# Power_Domain.net
KiCad netlist of a schematic drawn in Altium Designer
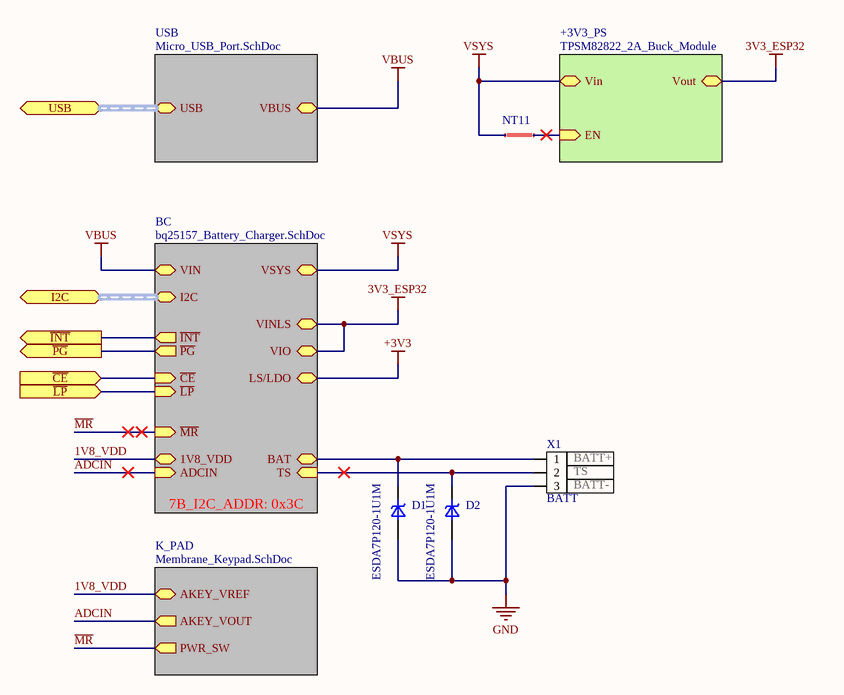
[diagram p0: Power_Domain.SchDoc]

(export (version "E")
  (design (tool "Eeschema 10.0.6"))
  (components
    (comp (ref "D1")
      (value "ESDA7P120-1U1M")
      (footprint "ST_QFN_1610")
      (description "11.5V Clamp 120A (8/20µs) Ipp Tvs Diode Surface Mount 1610")
      (fields (field (name "MANUFACTURER") "STMicroelectronics"))
      (libsource (lib "diodes_tvs") (part "TVS DIODE ESDA7P120-1U1M 5.5V 11.5V 1610"))
    )
    (comp (ref "D2")
      (value "ESDA7P120-1U1M")
      (footprint "ST_QFN_1610")
      (description "11.5V Clamp 120A (8/20µs) Ipp Tvs Diode Surface Mount 1610")
      (fields (field (name "MANUFACTURER") "STMicroelectronics"))
      (libsource (lib "diodes_tvs") (part "TVS DIODE ESDA7P120-1U1M 5.5V 11.5V 1610"))
    )
    (comp (ref "NT11")
      (value "Net Tie")
      (footprint "Net Tie 1x3mm")
      (libsource (lib "BLDC_Motor_Driver") (part "Net Tie Line"))
    )
    (comp (ref "X1")
      (value "BATT")
      (footprint "CONN_S3B-ZR_JST")
      (description "Connector Header Through Hole, Right Angle 3 position 0.059\" (1.50mm)")
      (fields
        (field (name "MANUFACTURER") "JST")
        (field (name "MANUFACTURER PART NUMBER") "S3B-ZR(LF)(SN)")
        (field (name "PIN_1") "BATT+")
        (field (name "PIN_2") "TS")
        (field (name "PIN_3") "BATT-")
      )
      (libsource (lib "connectors_header") (part "CONN HEADER TH R/A 3POS 1.5MM"))
    )
  )
  (nets
    (net (code "6") (name "/BAT") (class "Default")
      (node (ref "D1") (pin "1") (pinfunction "K_1") (pintype "passive"))
      (node (ref "X1") (pin "1") (pinfunction "1_1") (pintype "passive"))
    )
    (net (code "8") (name "/EN") (class "Default") (node (ref "NT11") (pin "1") (pintype "passive")))
    (net (code "14") (name "/TS") (class "Default")
      (node (ref "D2") (pin "1") (pinfunction "K_1") (pintype "passive"))
      (node (ref "X1") (pin "2") (pinfunction "2_2") (pintype "passive"))
    )
    (net (code "17") (name "GND") (class "Default")
      (node (ref "D1") (pin "2") (pinfunction "A_2") (pintype "passive"))
      (node (ref "D2") (pin "2") (pinfunction "A_2") (pintype "passive"))
      (node (ref "X1") (pin "3") (pinfunction "3_3") (pintype "passive"))
    )
    (net (code "19") (name "VSYS") (class "Default") (node (ref "NT11") (pin "2") (pintype "passive")))
  )
)
